# UART.net
KiCad netlist of a schematic drawn in Altium Designer
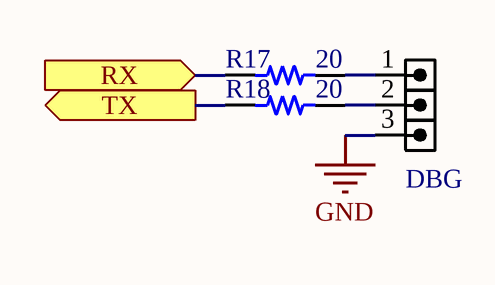
[diagram p0: UART.SchDoc]

(export (version "E")
  (design (tool "Eeschema 10.0.6"))
  (components
    (comp (ref "DBG")
      (value "HDR3")
      (footprint "HDR1SE_M_1X3")
      (description "HEADER, 1mm pitch, test, SMD")
      (libsource (lib "Conn Header") (part "HDRTST_1X3"))
    )
    (comp (ref "R17")
      (value "20")
      (footprint "RES 0603_1608")
      (description "SMT Resistor")
      (libsource (lib "Resistor") (part "Res 0603"))
    )
    (comp (ref "R18")
      (value "20")
      (footprint "RES 0603_1608")
      (description "SMT Resistor")
      (libsource (lib "Resistor") (part "Res 0603"))
    )
  )
  (nets
    (net (code "1") (name "/RX") (class "Default")
      (node (ref "R17") (pin "1") (pinfunction "1_1") (pintype "passive"))
    )
    (net (code "2") (name "/TX") (class "Default")
      (node (ref "R18") (pin "1") (pinfunction "1_1") (pintype "passive"))
    )
    (net (code "3") (name "GND") (class "Default")
      (node (ref "DBG") (pin "3") (pinfunction "3_3") (pintype "passive"))
    )
    (net (code "4") (name "Net-(DBG-Pad1)") (class "Default")
      (node (ref "DBG") (pin "1") (pinfunction "1_1") (pintype "passive"))
      (node (ref "R17") (pin "2") (pinfunction "2_2") (pintype "passive"))
    )
    (net (code "5") (name "Net-(DBG-Pad2)") (class "Default")
      (node (ref "DBG") (pin "2") (pinfunction "2_2") (pintype "passive"))
      (node (ref "R18") (pin "2") (pinfunction "2_2") (pintype "passive"))
    )
  )
)
